# Motor_Drive_Board_Header.net
KiCad netlist of a schematic drawn in Altium Designer
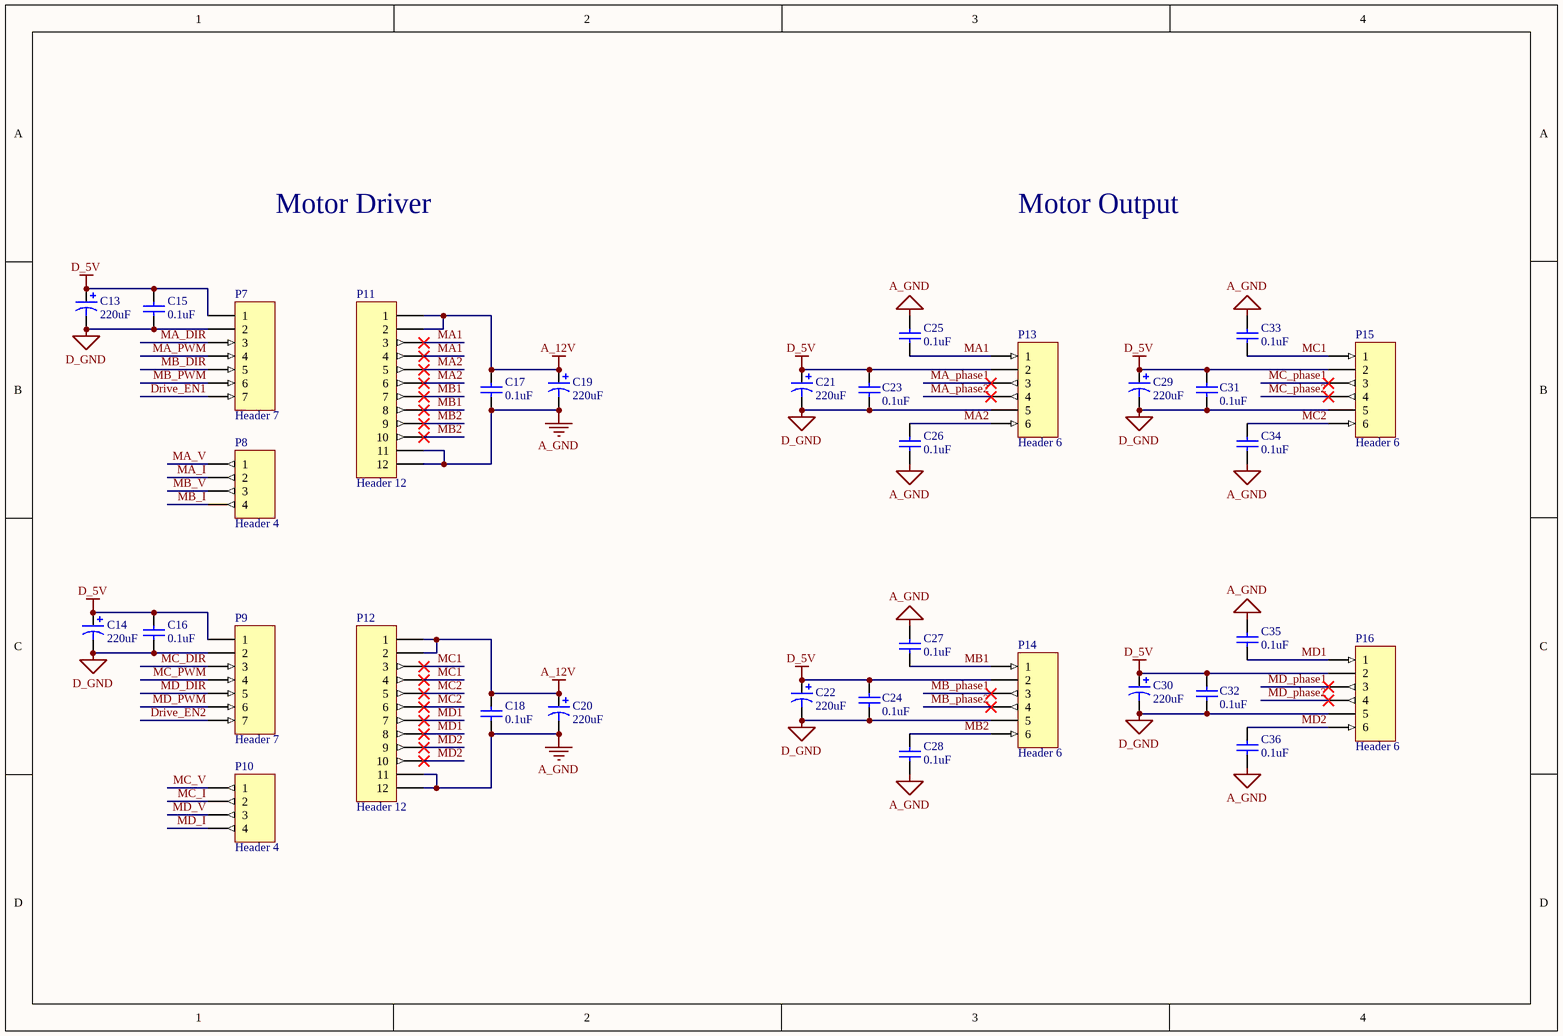
[diagram p0: Motor Drive Board Header.SchDoc]

(export (version "E")
  (design (tool "Eeschema 10.0.6"))
  (components
    (comp (ref "C13")
      (value "220uF")
      (footprint "OWMR:VZT221M1ETR-0607")
      (fields (field (name "PUBLISHER") "Altium Limited"))
      (libsource (lib "Miscellaneous Devices") (part "Cap Pol1"))
    )
    (comp (ref "C14")
      (value "220uF")
      (footprint "OWMR:VZT221M1ETR-0607")
      (fields (field (name "PUBLISHER") "Altium Limited"))
      (libsource (lib "Miscellaneous Devices") (part "Cap Pol1"))
    )
    (comp (ref "C15")
      (value "0.1uF")
      (footprint "OWMR:1210B104K500NT")
      (description "50V 100nF X7R ±10% 1210  Multilayer Ceramic Capacitors MLCC - SMD/SMT ROHS")
      (fields (field (name "PUBLISHER") "Altium Limited"))
      (libsource (lib "Miscellaneous Devices") (part "Cap Semi"))
    )
    (comp (ref "C16")
      (value "0.1uF")
      (footprint "OWMR:1210B104K500NT")
      (description "50V 100nF X7R ±10% 1210  Multilayer Ceramic Capacitors MLCC - SMD/SMT ROHS")
      (fields (field (name "PUBLISHER") "Altium Limited"))
      (libsource (lib "Miscellaneous Devices") (part "Cap Semi"))
    )
    (comp (ref "C17")
      (value "0.1uF")
      (footprint "OWMR:1210B104K500NT")
      (description "50V 100nF X7R ±10% 1210  Multilayer Ceramic Capacitors MLCC - SMD/SMT ROHS")
      (fields (field (name "PUBLISHER") "Altium Limited"))
      (libsource (lib "Miscellaneous Devices") (part "Cap Semi"))
    )
    (comp (ref "C18")
      (value "0.1uF")
      (footprint "OWMR:1210B104K500NT")
      (description "50V 100nF X7R ±10% 1210  Multilayer Ceramic Capacitors MLCC - SMD/SMT ROHS")
      (fields (field (name "PUBLISHER") "Altium Limited"))
      (libsource (lib "Miscellaneous Devices") (part "Cap Semi"))
    )
    (comp (ref "C19")
      (value "220uF")
      (footprint "OWMR:VZT221M1ETR-0607")
      (fields (field (name "PUBLISHER") "Altium Limited"))
      (libsource (lib "Miscellaneous Devices") (part "Cap Pol1"))
    )
    (comp (ref "C20")
      (value "220uF")
      (footprint "OWMR:VZT221M1ETR-0607")
      (fields (field (name "PUBLISHER") "Altium Limited"))
      (libsource (lib "Miscellaneous Devices") (part "Cap Pol1"))
    )
    (comp (ref "C21")
      (value "220uF")
      (footprint "OWMR:VZT221M1ETR-0607")
      (fields (field (name "PUBLISHER") "Altium Limited"))
      (libsource (lib "Miscellaneous Devices") (part "Cap Pol1"))
    )
    (comp (ref "C22")
      (value "220uF")
      (footprint "OWMR:VZT221M1ETR-0607")
      (fields (field (name "PUBLISHER") "Altium Limited"))
      (libsource (lib "Miscellaneous Devices") (part "Cap Pol1"))
    )
    (comp (ref "C23")
      (value "0.1uF")
      (footprint "OWMR:CL10B104KA8NNNC")
      (description "25V 100nF X7R ±10% 0603  Multilayer Ceramic Capacitors MLCC - SMD/SMT ROHS")
      (fields (field (name "PUBLISHER") "Altium Limited"))
      (libsource (lib "Miscellaneous Devices") (part "Cap Semi"))
    )
    (comp (ref "C24")
      (value "0.1uF")
      (footprint "OWMR:CL10B104KA8NNNC")
      (description "25V 100nF X7R ±10% 0603  Multilayer Ceramic Capacitors MLCC - SMD/SMT ROHS")
      (fields (field (name "PUBLISHER") "Altium Limited"))
      (libsource (lib "Miscellaneous Devices") (part "Cap Semi"))
    )
    (comp (ref "C25")
      (value "0.1uF")
      (footprint "OWMR:1210B104K500NT")
      (description "50V 100nF X7R ±10% 1210  Multilayer Ceramic Capacitors MLCC - SMD/SMT ROHS")
      (fields (field (name "PUBLISHER") "Altium Limited"))
      (libsource (lib "Miscellaneous Devices") (part "Cap Semi"))
    )
    (comp (ref "C26")
      (value "0.1uF")
      (footprint "OWMR:1210B104K500NT")
      (description "50V 100nF X7R ±10% 1210  Multilayer Ceramic Capacitors MLCC - SMD/SMT ROHS")
      (fields (field (name "PUBLISHER") "Altium Limited"))
      (libsource (lib "Miscellaneous Devices") (part "Cap Semi"))
    )
    (comp (ref "C27")
      (value "0.1uF")
      (footprint "OWMR:1210B104K500NT")
      (description "50V 100nF X7R ±10% 1210  Multilayer Ceramic Capacitors MLCC - SMD/SMT ROHS")
      (fields (field (name "PUBLISHER") "Altium Limited"))
      (libsource (lib "Miscellaneous Devices") (part "Cap Semi"))
    )
    (comp (ref "C28")
      (value "0.1uF")
      (footprint "OWMR:1210B104K500NT")
      (description "50V 100nF X7R ±10% 1210  Multilayer Ceramic Capacitors MLCC - SMD/SMT ROHS")
      (fields (field (name "PUBLISHER") "Altium Limited"))
      (libsource (lib "Miscellaneous Devices") (part "Cap Semi"))
    )
    (comp (ref "C29")
      (value "220uF")
      (footprint "OWMR:VZT221M1ETR-0607")
      (fields (field (name "PUBLISHER") "Altium Limited"))
      (libsource (lib "Miscellaneous Devices") (part "Cap Pol1"))
    )
    (comp (ref "C30")
      (value "220uF")
      (footprint "OWMR:VZT221M1ETR-0607")
      (fields (field (name "PUBLISHER") "Altium Limited"))
      (libsource (lib "Miscellaneous Devices") (part "Cap Pol1"))
    )
    (comp (ref "C31")
      (value "0.1uF")
      (footprint "OWMR:CL10B104KA8NNNC")
      (description "25V 100nF X7R ±10% 0603  Multilayer Ceramic Capacitors MLCC - SMD/SMT ROHS")
      (fields (field (name "PUBLISHER") "Altium Limited"))
      (libsource (lib "Miscellaneous Devices") (part "Cap Semi"))
    )
    (comp (ref "C32")
      (value "0.1uF")
      (footprint "OWMR:CL10B104KA8NNNC")
      (description "25V 100nF X7R ±10% 0603  Multilayer Ceramic Capacitors MLCC - SMD/SMT ROHS")
      (fields (field (name "PUBLISHER") "Altium Limited"))
      (libsource (lib "Miscellaneous Devices") (part "Cap Semi"))
    )
    (comp (ref "C33")
      (value "0.1uF")
      (footprint "OWMR:1210B104K500NT")
      (description "50V 100nF X7R ±10% 1210  Multilayer Ceramic Capacitors MLCC - SMD/SMT ROHS")
      (fields (field (name "PUBLISHER") "Altium Limited"))
      (libsource (lib "Miscellaneous Devices") (part "Cap Semi"))
    )
    (comp (ref "C34")
      (value "0.1uF")
      (footprint "OWMR:1210B104K500NT")
      (description "50V 100nF X7R ±10% 1210  Multilayer Ceramic Capacitors MLCC - SMD/SMT ROHS")
      (fields (field (name "PUBLISHER") "Altium Limited"))
      (libsource (lib "Miscellaneous Devices") (part "Cap Semi"))
    )
    (comp (ref "C35")
      (value "0.1uF")
      (footprint "OWMR:1210B104K500NT")
      (description "50V 100nF X7R ±10% 1210  Multilayer Ceramic Capacitors MLCC - SMD/SMT ROHS")
      (fields (field (name "PUBLISHER") "Altium Limited"))
      (libsource (lib "Miscellaneous Devices") (part "Cap Semi"))
    )
    (comp (ref "C36")
      (value "0.1uF")
      (footprint "OWMR:1210B104K500NT")
      (description "50V 100nF X7R ±10% 1210  Multilayer Ceramic Capacitors MLCC - SMD/SMT ROHS")
      (fields (field (name "PUBLISHER") "Altium Limited"))
      (libsource (lib "Miscellaneous Devices") (part "Cap Semi"))
    )
    (comp (ref "P7")
      (value "Header 7")
      (footprint "OWMR:KH-2.54FH-1X7P-H8.5")
      (fields (field (name "PUBLISHER") "Altium Limited"))
      (libsource (lib "Miscellaneous Connectors") (part "Header 7"))
    )
    (comp (ref "P8")
      (value "Header 4")
      (footprint "OWMR:KH-2.54FH-1X4P-H8.5")
      (fields (field (name "PUBLISHER") "Altium Limited"))
      (libsource (lib "Miscellaneous Connectors") (part "Header 4"))
    )
    (comp (ref "P9")
      (value "Header 7")
      (footprint "OWMR:KH-2.54FH-1X7P-H8.5")
      (fields (field (name "PUBLISHER") "Altium Limited"))
      (libsource (lib "Miscellaneous Connectors") (part "Header 7"))
    )
    (comp (ref "P10")
      (value "Header 4")
      (footprint "OWMR:KH-2.54FH-1X4P-H8.5")
      (fields (field (name "PUBLISHER") "Altium Limited"))
      (libsource (lib "Miscellaneous Connectors") (part "Header 4"))
    )
    (comp (ref "P11")
      (value "Header 12")
      (footprint "OWMR:KH-2.54FH-1X12P-H8.5 (Pad Linked)")
      (fields (field (name "PUBLISHER") "Altium Limited"))
      (libsource (lib "Miscellaneous Connectors") (part "Header 12"))
    )
    (comp (ref "P12")
      (value "Header 12")
      (footprint "OWMR:KH-2.54FH-1X12P-H8.5 (Pad Linked)")
      (fields (field (name "PUBLISHER") "Altium Limited"))
      (libsource (lib "Miscellaneous Connectors") (part "Header 12"))
    )
    (comp (ref "P13")
      (value "Header 6")
      (footprint "OWMR:B6B-XH-A(LF)(SN)")
      (description "1x6P XH 1 2.5mm 6 Brass Plugin,P=2.5mm  Wire To Board / Wire To Wire Connector ROHS")
      (fields (field (name "PUBLISHER") "Altium Limited"))
      (libsource (lib "Miscellaneous Connectors") (part "Header 6"))
    )
    (comp (ref "P14")
      (value "Header 6")
      (footprint "OWMR:B6B-XH-A(LF)(SN)")
      (description "1x6P XH 1 2.5mm 6 Brass Plugin,P=2.5mm  Wire To Board / Wire To Wire Connector ROHS")
      (fields (field (name "PUBLISHER") "Altium Limited"))
      (libsource (lib "Miscellaneous Connectors") (part "Header 6"))
    )
    (comp (ref "P15")
      (value "Header 6")
      (footprint "OWMR:B6B-XH-A(LF)(SN)")
      (description "1x6P XH 1 2.5mm 6 Brass Plugin,P=2.5mm  Wire To Board / Wire To Wire Connector ROHS")
      (fields (field (name "PUBLISHER") "Altium Limited"))
      (libsource (lib "Miscellaneous Connectors") (part "Header 6"))
    )
    (comp (ref "P16")
      (value "Header 6")
      (footprint "OWMR:B6B-XH-A(LF)(SN)")
      (description "1x6P XH 1 2.5mm 6 Brass Plugin,P=2.5mm  Wire To Board / Wire To Wire Connector ROHS")
      (fields (field (name "PUBLISHER") "Altium Limited"))
      (libsource (lib "Miscellaneous Connectors") (part "Header 6"))
    )
  )
  (nets
    (net (code "1") (name "/Drive_EN1") (class "Default")
      (node (ref "P7") (pin "7") (pinfunction "7_7") (pintype "input"))
    )
    (net (code "2") (name "/Drive_EN2") (class "Default")
      (node (ref "P9") (pin "7") (pinfunction "7_7") (pintype "input"))
    )
    (net (code "3") (name "/MA1") (class "Default")
      (node (ref "C25") (pin "1") (pinfunction "1_1") (pintype "passive"))
      (node (ref "P11") (pin "3") (pinfunction "3_3") (pintype "output"))
      (node (ref "P11") (pin "4") (pinfunction "4_4") (pintype "output"))
      (node (ref "P13") (pin "1") (pinfunction "1_1") (pintype "input"))
    )
    (net (code "4") (name "/MA2") (class "Default")
      (node (ref "C26") (pin "2") (pinfunction "2_2") (pintype "passive"))
      (node (ref "P11") (pin "5") (pinfunction "5_5") (pintype "output"))
      (node (ref "P11") (pin "6") (pinfunction "6_6") (pintype "output"))
      (node (ref "P13") (pin "6") (pinfunction "6_6") (pintype "input"))
    )
    (net (code "5") (name "/MA_DIR") (class "Default")
      (node (ref "P7") (pin "3") (pinfunction "3_3") (pintype "input"))
    )
    (net (code "6") (name "/MA_I") (class "Default")
      (node (ref "P8") (pin "2") (pinfunction "2_2") (pintype "output"))
    )
    (net (code "7") (name "/MA_PWM") (class "Default")
      (node (ref "P7") (pin "4") (pinfunction "4_4") (pintype "input"))
    )
    (net (code "8") (name "/MA_V") (class "Default")
      (node (ref "P8") (pin "1") (pinfunction "1_1") (pintype "output"))
    )
    (net (code "9") (name "/MA_phase1") (class "Default")
      (node (ref "P13") (pin "3") (pinfunction "3_3") (pintype "output+no_connect"))
    )
    (net (code "10") (name "/MA_phase2") (class "Default")
      (node (ref "P13") (pin "4") (pinfunction "4_4") (pintype "output+no_connect"))
    )
    (net (code "11") (name "/MB1") (class "Default")
      (node (ref "C27") (pin "1") (pinfunction "1_1") (pintype "passive"))
      (node (ref "P11") (pin "7") (pinfunction "7_7") (pintype "output"))
      (node (ref "P11") (pin "8") (pinfunction "8_8") (pintype "output"))
      (node (ref "P14") (pin "1") (pinfunction "1_1") (pintype "input"))
    )
    (net (code "12") (name "/MB2") (class "Default")
      (node (ref "C28") (pin "2") (pinfunction "2_2") (pintype "passive"))
      (node (ref "P11") (pin "10") (pinfunction "10_10") (pintype "output"))
      (node (ref "P11") (pin "9") (pinfunction "9_9") (pintype "output"))
      (node (ref "P14") (pin "6") (pinfunction "6_6") (pintype "input"))
    )
    (net (code "13") (name "/MB_DIR") (class "Default")
      (node (ref "P7") (pin "5") (pinfunction "5_5") (pintype "input"))
    )
    (net (code "14") (name "/MB_I") (class "Default")
      (node (ref "P8") (pin "4") (pinfunction "4_4") (pintype "output"))
    )
    (net (code "15") (name "/MB_PWM") (class "Default")
      (node (ref "P7") (pin "6") (pinfunction "6_6") (pintype "input"))
    )
    (net (code "16") (name "/MB_V") (class "Default")
      (node (ref "P8") (pin "3") (pinfunction "3_3") (pintype "output"))
    )
    (net (code "17") (name "/MB_phase1") (class "Default")
      (node (ref "P14") (pin "3") (pinfunction "3_3") (pintype "output+no_connect"))
    )
    (net (code "18") (name "/MB_phase2") (class "Default")
      (node (ref "P14") (pin "4") (pinfunction "4_4") (pintype "output+no_connect"))
    )
    (net (code "19") (name "/MC1") (class "Default")
      (node (ref "C33") (pin "1") (pinfunction "1_1") (pintype "passive"))
      (node (ref "P12") (pin "3") (pinfunction "3_3") (pintype "output"))
      (node (ref "P12") (pin "4") (pinfunction "4_4") (pintype "output"))
      (node (ref "P15") (pin "1") (pinfunction "1_1") (pintype "input"))
    )
    (net (code "20") (name "/MC2") (class "Default")
      (node (ref "C34") (pin "2") (pinfunction "2_2") (pintype "passive"))
      (node (ref "P12") (pin "5") (pinfunction "5_5") (pintype "output"))
      (node (ref "P12") (pin "6") (pinfunction "6_6") (pintype "output"))
      (node (ref "P15") (pin "6") (pinfunction "6_6") (pintype "input"))
    )
    (net (code "21") (name "/MC_DIR") (class "Default")
      (node (ref "P9") (pin "3") (pinfunction "3_3") (pintype "input"))
    )
    (net (code "22") (name "/MC_I") (class "Default")
      (node (ref "P10") (pin "2") (pinfunction "2_2") (pintype "output"))
    )
    (net (code "23") (name "/MC_PWM") (class "Default")
      (node (ref "P9") (pin "4") (pinfunction "4_4") (pintype "input"))
    )
    (net (code "24") (name "/MC_V") (class "Default")
      (node (ref "P10") (pin "1") (pinfunction "1_1") (pintype "output"))
    )
    (net (code "25") (name "/MC_phase1") (class "Default")
      (node (ref "P15") (pin "3") (pinfunction "3_3") (pintype "output+no_connect"))
    )
    (net (code "26") (name "/MC_phase2") (class "Default")
      (node (ref "P15") (pin "4") (pinfunction "4_4") (pintype "output+no_connect"))
    )
    (net (code "27") (name "/MD1") (class "Default")
      (node (ref "C35") (pin "1") (pinfunction "1_1") (pintype "passive"))
      (node (ref "P12") (pin "7") (pinfunction "7_7") (pintype "output"))
      (node (ref "P12") (pin "8") (pinfunction "8_8") (pintype "output"))
      (node (ref "P16") (pin "1") (pinfunction "1_1") (pintype "input"))
    )
    (net (code "28") (name "/MD2") (class "Default")
      (node (ref "C36") (pin "2") (pinfunction "2_2") (pintype "passive"))
      (node (ref "P12") (pin "10") (pinfunction "10_10") (pintype "output"))
      (node (ref "P12") (pin "9") (pinfunction "9_9") (pintype "output"))
      (node (ref "P16") (pin "6") (pinfunction "6_6") (pintype "input"))
    )
    (net (code "29") (name "/MD_DIR") (class "Default")
      (node (ref "P9") (pin "5") (pinfunction "5_5") (pintype "input"))
    )
    (net (code "30") (name "/MD_I") (class "Default")
      (node (ref "P10") (pin "4") (pinfunction "4_4") (pintype "output"))
    )
    (net (code "31") (name "/MD_PWM") (class "Default")
      (node (ref "P9") (pin "6") (pinfunction "6_6") (pintype "input"))
    )
    (net (code "32") (name "/MD_V") (class "Default")
      (node (ref "P10") (pin "3") (pinfunction "3_3") (pintype "output"))
    )
    (net (code "33") (name "/MD_phase1") (class "Default")
      (node (ref "P16") (pin "3") (pinfunction "3_3") (pintype "output+no_connect"))
    )
    (net (code "34") (name "/MD_phase2") (class "Default")
      (node (ref "P16") (pin "4") (pinfunction "4_4") (pintype "output+no_connect"))
    )
    (net (code "35") (name "A_12V") (class "Default")
      (node (ref "C17") (pin "2") (pinfunction "2_2") (pintype "passive"))
      (node (ref "C18") (pin "2") (pinfunction "2_2") (pintype "passive"))
      (node (ref "C19") (pin "1") (pinfunction "1_1") (pintype "passive"))
      (node (ref "C20") (pin "1") (pinfunction "1_1") (pintype "passive"))
      (node (ref "P11") (pin "1") (pinfunction "1_1") (pintype "power_in"))
      (node (ref "P11") (pin "2") (pinfunction "2_2") (pintype "power_in"))
      (node (ref "P12") (pin "1") (pinfunction "1_1") (pintype "power_in"))
      (node (ref "P12") (pin "2") (pinfunction "2_2") (pintype "power_in"))
    )
    (net (code "36") (name "A_GND") (class "Default")
      (node (ref "C17") (pin "1") (pinfunction "1_1") (pintype "passive"))
      (node (ref "C18") (pin "1") (pinfunction "1_1") (pintype "passive"))
      (node (ref "C19") (pin "2") (pinfunction "2_2") (pintype "passive"))
      (node (ref "C20") (pin "2") (pinfunction "2_2") (pintype "passive"))
      (node (ref "C25") (pin "2") (pinfunction "2_2") (pintype "passive"))
      (node (ref "C26") (pin "1") (pinfunction "1_1") (pintype "passive"))
      (node (ref "C27") (pin "2") (pinfunction "2_2") (pintype "passive"))
      (node (ref "C28") (pin "1") (pinfunction "1_1") (pintype "passive"))
      (node (ref "C33") (pin "2") (pinfunction "2_2") (pintype "passive"))
      (node (ref "C34") (pin "1") (pinfunction "1_1") (pintype "passive"))
      (node (ref "C35") (pin "2") (pinfunction "2_2") (pintype "passive"))
      (node (ref "C36") (pin "1") (pinfunction "1_1") (pintype "passive"))
      (node (ref "P11") (pin "11") (pinfunction "11_11") (pintype "power_in"))
      (node (ref "P11") (pin "12") (pinfunction "12_12") (pintype "power_in"))
      (node (ref "P12") (pin "11") (pinfunction "11_11") (pintype "power_in"))
      (node (ref "P12") (pin "12") (pinfunction "12_12") (pintype "power_in"))
    )
    (net (code "37") (name "D_5V") (class "Default")
      (node (ref "C13") (pin "1") (pinfunction "1_1") (pintype "passive"))
      (node (ref "C14") (pin "1") (pinfunction "1_1") (pintype "passive"))
      (node (ref "C15") (pin "2") (pinfunction "2_2") (pintype "passive"))
      (node (ref "C16") (pin "2") (pinfunction "2_2") (pintype "passive"))
      (node (ref "C21") (pin "1") (pinfunction "1_1") (pintype "passive"))
      (node (ref "C22") (pin "1") (pinfunction "1_1") (pintype "passive"))
      (node (ref "C23") (pin "2") (pinfunction "2_2") (pintype "passive"))
      (node (ref "C24") (pin "2") (pinfunction "2_2") (pintype "passive"))
      (node (ref "C29") (pin "1") (pinfunction "1_1") (pintype "passive"))
      (node (ref "C30") (pin "1") (pinfunction "1_1") (pintype "passive"))
      (node (ref "C31") (pin "2") (pinfunction "2_2") (pintype "passive"))
      (node (ref "C32") (pin "2") (pinfunction "2_2") (pintype "passive"))
      (node (ref "P13") (pin "2") (pinfunction "2_2") (pintype "power_in"))
      (node (ref "P14") (pin "2") (pinfunction "2_2") (pintype "power_in"))
      (node (ref "P15") (pin "2") (pinfunction "2_2") (pintype "power_in"))
      (node (ref "P16") (pin "2") (pinfunction "2_2") (pintype "power_in"))
      (node (ref "P7") (pin "1") (pinfunction "1_1") (pintype "power_in"))
      (node (ref "P9") (pin "1") (pinfunction "1_1") (pintype "power_in"))
    )
    (net (code "38") (name "D_GND") (class "Default")
      (node (ref "C13") (pin "2") (pinfunction "2_2") (pintype "passive"))
      (node (ref "C14") (pin "2") (pinfunction "2_2") (pintype "passive"))
      (node (ref "C15") (pin "1") (pinfunction "1_1") (pintype "passive"))
      (node (ref "C16") (pin "1") (pinfunction "1_1") (pintype "passive"))
      (node (ref "C21") (pin "2") (pinfunction "2_2") (pintype "passive"))
      (node (ref "C22") (pin "2") (pinfunction "2_2") (pintype "passive"))
      (node (ref "C23") (pin "1") (pinfunction "1_1") (pintype "passive"))
      (node (ref "C24") (pin "1") (pinfunction "1_1") (pintype "passive"))
      (node (ref "C29") (pin "2") (pinfunction "2_2") (pintype "passive"))
      (node (ref "C30") (pin "2") (pinfunction "2_2") (pintype "passive"))
      (node (ref "C31") (pin "1") (pinfunction "1_1") (pintype "passive"))
      (node (ref "C32") (pin "1") (pinfunction "1_1") (pintype "passive"))
      (node (ref "P13") (pin "5") (pinfunction "5_5") (pintype "power_in"))
      (node (ref "P14") (pin "5") (pinfunction "5_5") (pintype "power_in"))
      (node (ref "P15") (pin "5") (pinfunction "5_5") (pintype "power_in"))
      (node (ref "P16") (pin "5") (pinfunction "5_5") (pintype "power_in"))
      (node (ref "P7") (pin "2") (pinfunction "2_2") (pintype "power_in"))
      (node (ref "P9") (pin "2") (pinfunction "2_2") (pintype "power_in"))
    )
  )
)
